# pcb_1_0.net
KiCad netlist of a schematic drawn in EAGLE
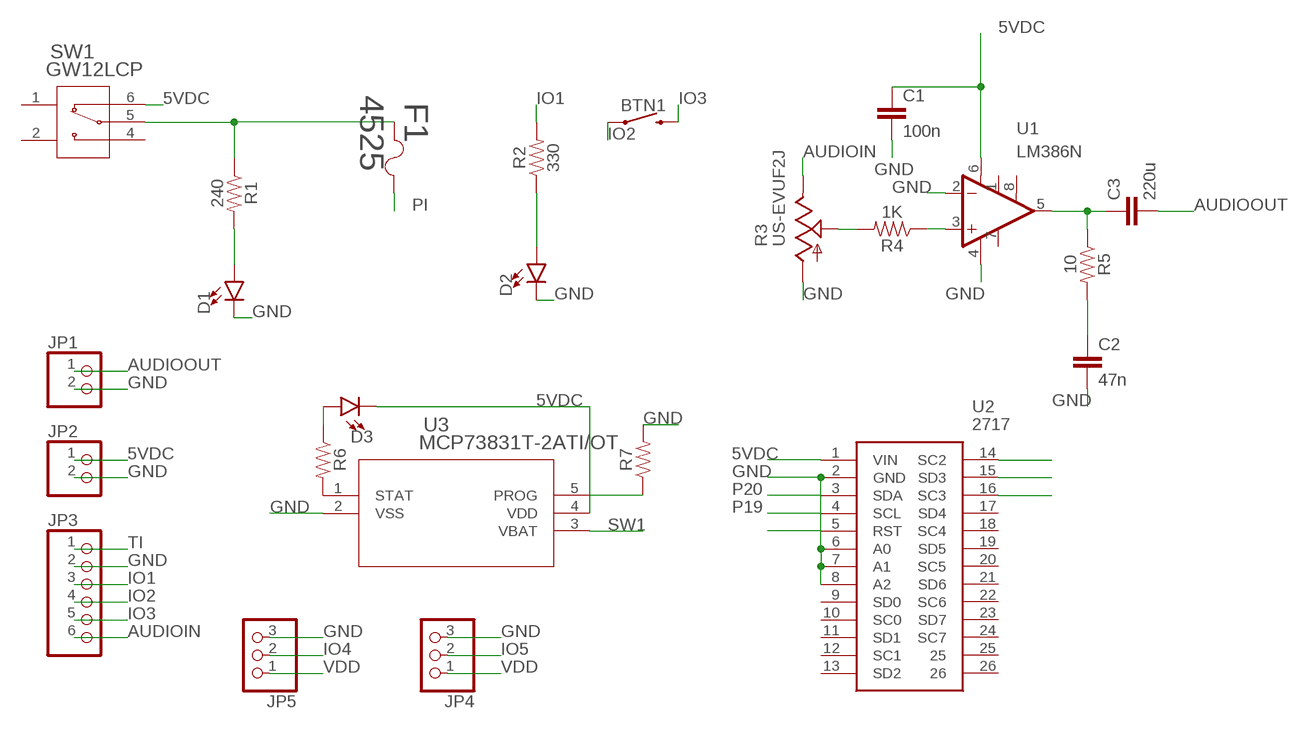
[diagram p0: schematic, sheet 1]

(export (version "E")
  (design (tool "Eeschema 10.0.6"))
  (components
    (comp (ref "BTN1")
      (value "MOMENTARY-SWITCH-SPST-PTH-12MM")
      (footprint "eagle-import:TACTILE_SWITCH_PTH_12MM")
      (libsource (lib "eagle-import") (part "MOMENTARY-SWITCH-SPST-PTH-12MM"))
    )
    (comp (ref "C1")
      (value "100n")
      (footprint "eagle-import:CAP-PTH-SMALL-KIT")
      (libsource (lib "eagle-import") (part "0.1UF-KIT-EZ-50V-20%"))
    )
    (comp (ref "C2")
      (value "47n")
      (footprint "eagle-import:CAP-PTH-SMALL-KIT")
      (libsource (lib "eagle-import") (part "0.1UF-KIT-EZ-50V-20%"))
    )
    (comp (ref "C3")
      (value "220u")
      (footprint "eagle-import:CAP-PTH-SMALL-KIT")
      (libsource (lib "eagle-import") (part "0.1UF-KIT-EZ-50V-20%"))
    )
    (comp (ref "D1")
      (value "LED5MM")
      (footprint "eagle-import:LED_5MM")
      (libsource (lib "eagle-import") (part "LED5MM"))
    )
    (comp (ref "D2")
      (value "LED5MM")
      (footprint "eagle-import:LED_5MM")
      (libsource (lib "eagle-import") (part "LED5MM"))
    )
    (comp (ref "D3")
      (value "LED5MM")
      (footprint "eagle-import:LED_5MM")
      (libsource (lib "eagle-import") (part "LED5MM"))
    )
    (comp (ref "F1")
      (value "4525")
      (footprint "eagle-import:FUSE_4525_KEY")
      (fields (field (name "COPYRIGHT") "Copyright (C) 2022 Ultra Librarian. All rights reserved."))
      (libsource (lib "eagle-import") (part "4525"))
    )
    (comp (ref "JP1")
      (value "PINHD-1X2")
      (footprint "eagle-import:1X02")
      (libsource (lib "eagle-import") (part "PINHD-1X2"))
    )
    (comp (ref "JP2")
      (value "PINHD-1X2")
      (footprint "eagle-import:1X02")
      (libsource (lib "eagle-import") (part "PINHD-1X2"))
    )
    (comp (ref "JP3")
      (value "PINHD-1X6")
      (footprint "eagle-import:1X06")
      (libsource (lib "eagle-import") (part "PINHD-1X6"))
    )
    (comp (ref "JP4")
      (value "PINHD-1X3")
      (footprint "eagle-import:1X03")
      (libsource (lib "eagle-import") (part "PINHD-1X3"))
    )
    (comp (ref "JP5")
      (value "PINHD-1X3")
      (footprint "eagle-import:1X03")
      (libsource (lib "eagle-import") (part "PINHD-1X3"))
    )
    (comp (ref "R1")
      (value "240")
      (footprint "eagle-import:AXIAL-0.3-KIT")
      (libsource (lib "eagle-import") (part "1KOHM-HORIZ_KIT-1/4W-1%"))
    )
    (comp (ref "R2")
      (value "330")
      (footprint "eagle-import:AXIAL-0.3-KIT")
      (libsource (lib "eagle-import") (part "1KOHM-HORIZ_KIT-1/4W-1%"))
    )
    (comp (ref "R3")
      (value "US-EVUF2J")
      (footprint "eagle-import:EVUFXJ")
      (libsource (lib "eagle-import") (part "US-EVUF2J"))
    )
    (comp (ref "R4")
      (value "1K")
      (footprint "eagle-import:AXIAL-0.3-KIT")
      (libsource (lib "eagle-import") (part "1KOHM-HORIZ_KIT-1/4W-1%"))
    )
    (comp (ref "R5")
      (value "10")
      (footprint "eagle-import:AXIAL-0.3-KIT")
      (libsource (lib "eagle-import") (part "1KOHM-HORIZ_KIT-1/4W-1%"))
    )
    (comp (ref "R6")
      (value "470")
      (footprint "eagle-import:AXIAL-0.3-KIT")
      (libsource (lib "eagle-import") (part "1KOHM-HORIZ_KIT-1/4W-1%"))
    )
    (comp (ref "R7")
      (value "470")
      (footprint "eagle-import:AXIAL-0.3-KIT")
      (libsource (lib "eagle-import") (part "1KOHM-HORIZ_KIT-1/4W-1%"))
    )
    (comp (ref "SW1")
      (value "GW12LCP")
      (footprint "eagle-import:GW12LCP_NKK")
      (fields (field (name "COPYRIGHT") "Copyright (C) 2022 Ultra Librarian. All rights reserved."))
      (libsource (lib "eagle-import") (part "GW12LCP"))
    )
    (comp (ref "U1")
      (value "LM386N")
      (footprint "eagle-import:DIP08")
      (libsource (lib "eagle-import") (part "LM386"))
    )
    (comp (ref "U2")
      (value "2717")
      (footprint "eagle-import:2717")
      (fields (field (name "MOUSER_PART_NUMBER") "485-2717"))
      (libsource (lib "eagle-import") (part "2717"))
    )
    (comp (ref "U3")
      (value "MCP73831T-2ATI/OT")
      (footprint "eagle-import:SOT-23-5_MC_MCH")
      (fields (field (name "COPYRIGHT") "Copyright (C) 2023 Ultra Librarian. All rights reserved."))
      (libsource (lib "eagle-import") (part "MCP73831T-2ATI/OT"))
    )
  )
  (nets
    (net (code "1") (name "/5VDC") (class "Default")
      (node (ref "C1") (pin "1") (pinfunction "1_1") (pintype "passive"))
      (node (ref "D3") (pin "K") (pinfunction "C_K") (pintype "passive"))
      (node (ref "JP2") (pin "1") (pinfunction "1_1") (pintype "passive"))
      (node (ref "SW1") (pin "6") (pinfunction "6_6") (pintype "passive"))
      (node (ref "U1") (pin "6") (pinfunction "V+_6") (pintype "power_in"))
      (node (ref "U2") (pin "1") (pinfunction "VIN_1") (pintype "bidirectional"))
      (node (ref "U3") (pin "4") (pinfunction "VDD_4") (pintype "passive"))
    )
    (net (code "2") (name "/AUDIOIN") (class "Default")
      (node (ref "JP3") (pin "6") (pinfunction "6_6") (pintype "passive"))
      (node (ref "R3") (pin "3") (pinfunction "E_3") (pintype "passive"))
    )
    (net (code "3") (name "/AUDIOOUT") (class "Default")
      (node (ref "C3") (pin "2") (pinfunction "2_2") (pintype "passive"))
      (node (ref "JP1") (pin "1") (pinfunction "1_1") (pintype "passive"))
    )
    (net (code "4") (name "/GND") (class "Default")
      (node (ref "C1") (pin "2") (pinfunction "2_2") (pintype "passive"))
      (node (ref "C2") (pin "2") (pinfunction "2_2") (pintype "passive"))
      (node (ref "D1") (pin "K") (pinfunction "C_K") (pintype "passive"))
      (node (ref "D2") (pin "K") (pinfunction "C_K") (pintype "passive"))
      (node (ref "JP1") (pin "2") (pinfunction "2_2") (pintype "passive"))
      (node (ref "JP2") (pin "2") (pinfunction "2_2") (pintype "passive"))
      (node (ref "JP3") (pin "2") (pinfunction "2_2") (pintype "passive"))
      (node (ref "JP4") (pin "3") (pinfunction "3_3") (pintype "passive"))
      (node (ref "JP5") (pin "3") (pinfunction "3_3") (pintype "passive"))
      (node (ref "R3") (pin "1") (pinfunction "A_1") (pintype "passive"))
      (node (ref "R7") (pin "P$2") (pinfunction "2_P$2") (pintype "passive"))
      (node (ref "U1") (pin "2") (pinfunction "-IN_2") (pintype "input"))
      (node (ref "U1") (pin "4") (pinfunction "V-_4") (pintype "power_in"))
      (node (ref "U2") (pin "2") (pinfunction "GND_2") (pintype "bidirectional"))
      (node (ref "U2") (pin "6") (pinfunction "A0_6") (pintype "bidirectional"))
      (node (ref "U2") (pin "7") (pinfunction "A1_7") (pintype "bidirectional"))
      (node (ref "U2") (pin "8") (pinfunction "A2_8") (pintype "bidirectional"))
      (node (ref "U3") (pin "2") (pinfunction "VSS_2") (pintype "passive"))
    )
    (net (code "5") (name "/IO1") (class "Default")
      (node (ref "JP3") (pin "3") (pinfunction "3_3") (pintype "passive"))
      (node (ref "R2") (pin "P$2") (pinfunction "2_P$2") (pintype "passive"))
    )
    (net (code "6") (name "/IO2") (class "Default")
      (node (ref "BTN1") (pin "1") (pinfunction "1_1") (pintype "passive"))
      (node (ref "JP3") (pin "4") (pinfunction "4_4") (pintype "passive"))
    )
    (net (code "7") (name "/IO3") (class "Default")
      (node (ref "BTN1") (pin "3") (pinfunction "2_3") (pintype "passive"))
      (node (ref "JP3") (pin "5") (pinfunction "5_5") (pintype "passive"))
    )
    (net (code "8") (name "/IO4") (class "Default")
      (node (ref "JP5") (pin "2") (pinfunction "2_2") (pintype "passive"))
    )
    (net (code "9") (name "/IO5") (class "Default")
      (node (ref "JP4") (pin "2") (pinfunction "2_2") (pintype "passive"))
    )
    (net (code "10") (name "/P19") (class "Default")
      (node (ref "U2") (pin "16") (pinfunction "SC3_16") (pintype "bidirectional"))
    )
    (net (code "11") (name "/P20") (class "Default")
      (node (ref "U2") (pin "15") (pinfunction "SD3_15") (pintype "bidirectional"))
    )
    (net (code "12") (name "/PI") (class "Default")
      (node (ref "F1") (pin "2") (pinfunction "2_2") (pintype "passive"))
    )
    (net (code "13") (name "/SW1") (class "Default")
      (node (ref "U3") (pin "3") (pinfunction "VBAT_3") (pintype "passive"))
    )
    (net (code "14") (name "/TI") (class "Default")
      (node (ref "JP3") (pin "1") (pinfunction "1_1") (pintype "passive"))
    )
    (net (code "15") (name "/VDD") (class "Default")
      (node (ref "JP4") (pin "1") (pinfunction "1_1") (pintype "passive"))
      (node (ref "JP5") (pin "1") (pinfunction "1_1") (pintype "passive"))
    )
    (net (code "16") (name "Net-(R1-1)") (class "Default")
      (node (ref "F1") (pin "1") (pinfunction "1_1") (pintype "passive"))
      (node (ref "R1") (pin "P$1") (pinfunction "1_P$1") (pintype "passive"))
      (node (ref "SW1") (pin "5") (pinfunction "5_5") (pintype "passive"))
    )
    (net (code "17") (name "Net-(R1-2)") (class "Default")
      (node (ref "D1") (pin "A") (pinfunction "A_A") (pintype "passive"))
      (node (ref "R1") (pin "P$2") (pinfunction "2_P$2") (pintype "passive"))
    )
    (net (code "18") (name "Net-(R2-1)") (class "Default")
      (node (ref "D2") (pin "A") (pinfunction "A_A") (pintype "passive"))
      (node (ref "R2") (pin "P$1") (pinfunction "1_P$1") (pintype "passive"))
    )
    (net (code "19") (name "Net-(R3-S)") (class "Default")
      (node (ref "R3") (pin "2") (pinfunction "S_2") (pintype "passive"))
      (node (ref "R4") (pin "P$2") (pinfunction "2_P$2") (pintype "passive"))
    )
    (net (code "20") (name "Net-(R4-1)") (class "Default")
      (node (ref "R4") (pin "P$1") (pinfunction "1_P$1") (pintype "passive"))
      (node (ref "U1") (pin "3") (pinfunction "+IN_3") (pintype "input"))
    )
    (net (code "21") (name "Net-(R5-1)") (class "Default")
      (node (ref "C3") (pin "1") (pinfunction "1_1") (pintype "passive"))
      (node (ref "R5") (pin "P$1") (pinfunction "1_P$1") (pintype "passive"))
      (node (ref "U1") (pin "5") (pinfunction "OUT_5") (pintype "output"))
    )
    (net (code "22") (name "Net-(R5-2)") (class "Default")
      (node (ref "C2") (pin "1") (pinfunction "1_1") (pintype "passive"))
      (node (ref "R5") (pin "P$2") (pinfunction "2_P$2") (pintype "passive"))
    )
    (net (code "23") (name "Net-(R6-1)") (class "Default")
      (node (ref "D3") (pin "A") (pinfunction "A_A") (pintype "passive"))
      (node (ref "R6") (pin "P$1") (pinfunction "1_P$1") (pintype "passive"))
    )
    (net (code "24") (name "Net-(R6-2)") (class "Default")
      (node (ref "R6") (pin "P$2") (pinfunction "2_P$2") (pintype "passive"))
      (node (ref "U3") (pin "1") (pinfunction "STAT_1") (pintype "passive"))
    )
    (net (code "25") (name "Net-(R7-1)") (class "Default")
      (node (ref "R7") (pin "P$1") (pinfunction "1_P$1") (pintype "passive"))
      (node (ref "U3") (pin "5") (pinfunction "PROG_5") (pintype "passive"))
    )
    (net (code "26") (name "unconnected-(SW1-3-Pad2)") (class "Default")
      (node (ref "SW1") (pin "2") (pinfunction "3_2") (pintype "passive"))
    )
    (net (code "27") (name "unconnected-(SW1-Pad1)") (class "Default")
      (node (ref "SW1") (pin "1") (pinfunction "1_1") (pintype "passive"))
    )
    (net (code "28") (name "unconnected-(SW1-Pad4)") (class "Default")
      (node (ref "SW1") (pin "4") (pinfunction "4_4") (pintype "passive"))
    )
    (net (code "29") (name "unconnected-(U1-BP-Pad7)") (class "Default")
      (node (ref "U1") (pin "7") (pinfunction "BP_7") (pintype "bidirectional"))
    )
    (net (code "30") (name "unconnected-(U1-GAIN-Pad1)") (class "Default")
      (node (ref "U1") (pin "1") (pinfunction "GAIN_1") (pintype "bidirectional"))
    )
    (net (code "31") (name "unconnected-(U1-GAIN-Pad8)") (class "Default")
      (node (ref "U1") (pin "8") (pinfunction "GAIN_8") (pintype "bidirectional"))
    )
    (net (code "32") (name "unconnected-(U2-Pad25)") (class "Default")
      (node (ref "U2") (pin "25") (pinfunction "25_25") (pintype "bidirectional"))
    )
    (net (code "33") (name "unconnected-(U2-Pad26)") (class "Default")
      (node (ref "U2") (pin "26") (pinfunction "26_26") (pintype "bidirectional"))
    )
    (net (code "34") (name "unconnected-(U2-RST-Pad5)") (class "Default")
      (node (ref "U2") (pin "5") (pinfunction "RST_5") (pintype "bidirectional"))
    )
    (net (code "35") (name "unconnected-(U2-SC0-Pad10)") (class "Default")
      (node (ref "U2") (pin "10") (pinfunction "SC0_10") (pintype "bidirectional"))
    )
    (net (code "36") (name "unconnected-(U2-SC1-Pad12)") (class "Default")
      (node (ref "U2") (pin "12") (pinfunction "SC1_12") (pintype "bidirectional"))
    )
    (net (code "37") (name "unconnected-(U2-SC2-Pad14)") (class "Default")
      (node (ref "U2") (pin "14") (pinfunction "SC2_14") (pintype "bidirectional"))
    )
    (net (code "38") (name "unconnected-(U2-SC4-Pad18)") (class "Default")
      (node (ref "U2") (pin "18") (pinfunction "SC4_18") (pintype "bidirectional"))
    )
    (net (code "39") (name "unconnected-(U2-SC5-Pad20)") (class "Default")
      (node (ref "U2") (pin "20") (pinfunction "SC5_20") (pintype "bidirectional"))
    )
    (net (code "40") (name "unconnected-(U2-SC6-Pad22)") (class "Default")
      (node (ref "U2") (pin "22") (pinfunction "SC6_22") (pintype "bidirectional"))
    )
    (net (code "41") (name "unconnected-(U2-SC7-Pad24)") (class "Default")
      (node (ref "U2") (pin "24") (pinfunction "SC7_24") (pintype "bidirectional"))
    )
    (net (code "42") (name "unconnected-(U2-SCL-Pad4)") (class "Default")
      (node (ref "U2") (pin "4") (pinfunction "SCL_4") (pintype "bidirectional"))
    )
    (net (code "43") (name "unconnected-(U2-SD0-Pad9)") (class "Default")
      (node (ref "U2") (pin "9") (pinfunction "SD0_9") (pintype "bidirectional"))
    )
    (net (code "44") (name "unconnected-(U2-SD1-Pad11)") (class "Default")
      (node (ref "U2") (pin "11") (pinfunction "SD1_11") (pintype "bidirectional"))
    )
    (net (code "45") (name "unconnected-(U2-SD2-Pad13)") (class "Default")
      (node (ref "U2") (pin "13") (pinfunction "SD2_13") (pintype "bidirectional"))
    )
    (net (code "46") (name "unconnected-(U2-SD4-Pad17)") (class "Default")
      (node (ref "U2") (pin "17") (pinfunction "SD4_17") (pintype "bidirectional"))
    )
    (net (code "47") (name "unconnected-(U2-SD5-Pad19)") (class "Default")
      (node (ref "U2") (pin "19") (pinfunction "SD5_19") (pintype "bidirectional"))
    )
    (net (code "48") (name "unconnected-(U2-SD6-Pad21)") (class "Default")
      (node (ref "U2") (pin "21") (pinfunction "SD6_21") (pintype "bidirectional"))
    )
    (net (code "49") (name "unconnected-(U2-SD7-Pad23)") (class "Default")
      (node (ref "U2") (pin "23") (pinfunction "SD7_23") (pintype "bidirectional"))
    )
    (net (code "50") (name "unconnected-(U2-SDA-Pad3)") (class "Default")
      (node (ref "U2") (pin "3") (pinfunction "SDA_3") (pintype "bidirectional"))
    )
  )
)
